# LCDTFT_CTRL_BT817_818.net
KiCad netlist of a schematic drawn in Altium Designer
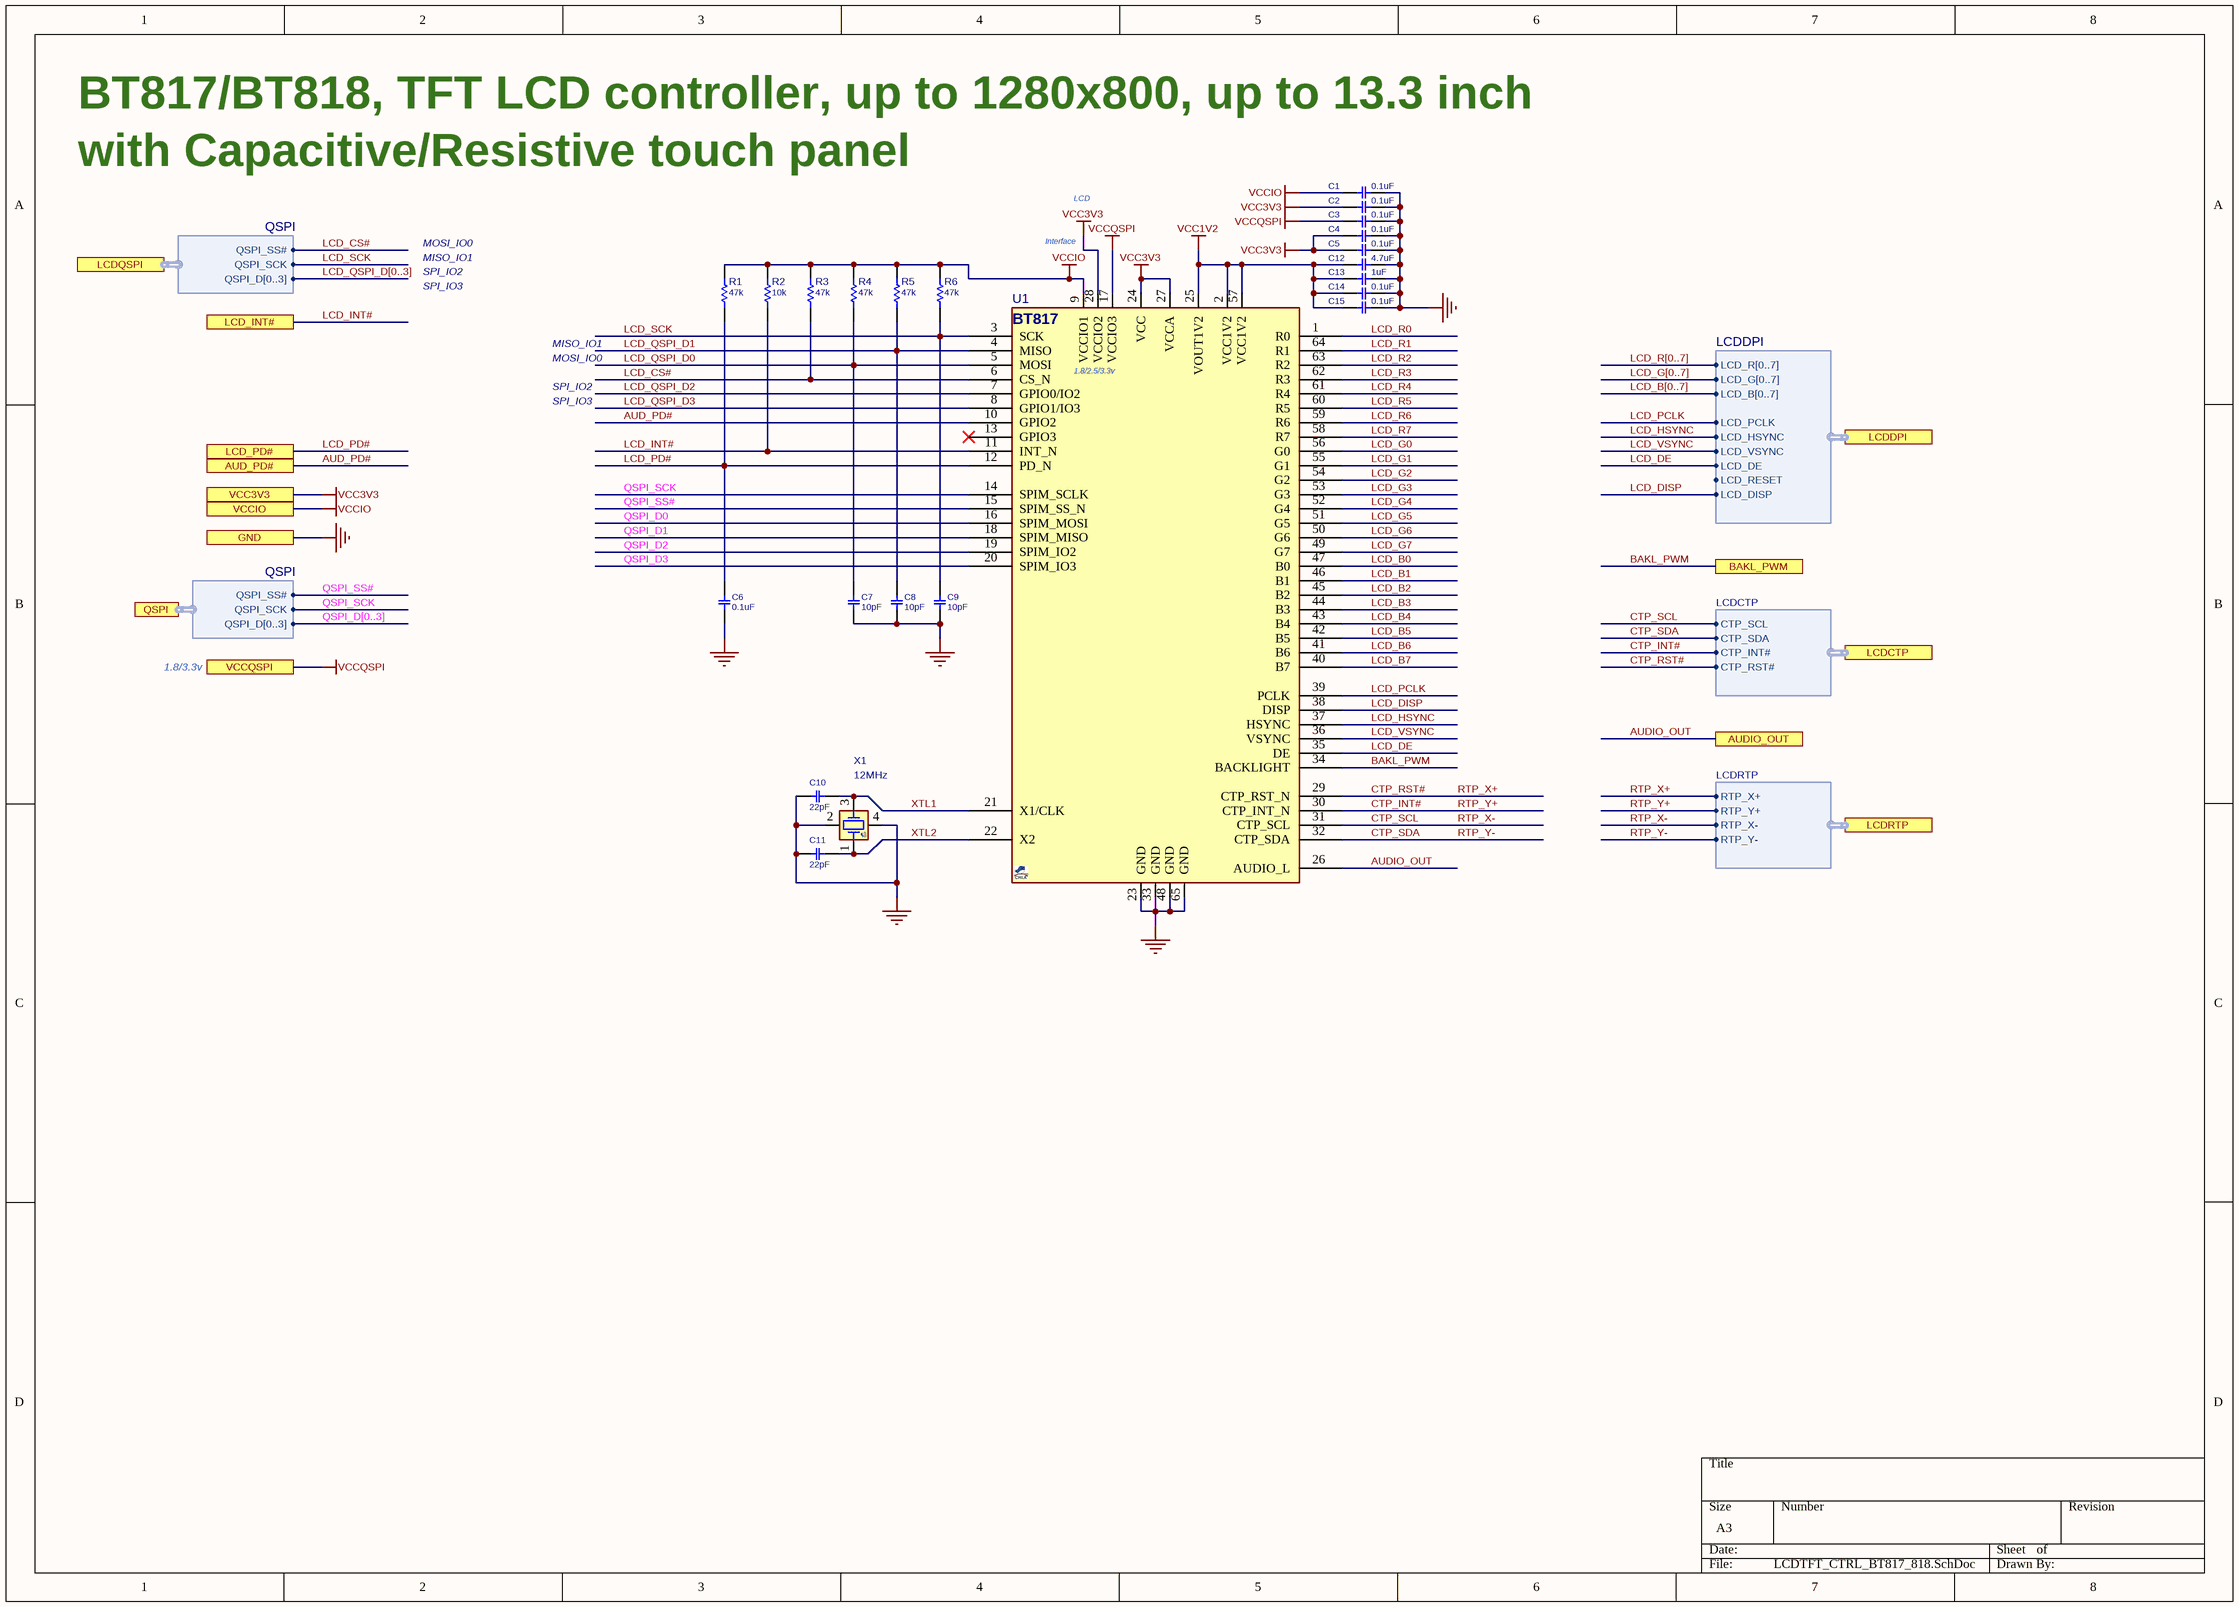
[diagram p0: LCDTFT_CTRL_BT817_818.SchDoc]

(export (version "E")
  (design (tool "Eeschema 10.0.6"))
  (components
    (comp (ref "C1")
      (value "0.1uF")
      (footprint "C0402")
      (description "CAP, MLCC")
      (fields (field (name "MANF_P#") "GRM155R71H104KE14D") (field (name "MANF") "Murata"))
      (libsource (lib "passive_smd") (part "CAP_SMD_MLCC"))
    )
    (comp (ref "C2")
      (value "0.1uF")
      (footprint "C0402")
      (description "CAP, MLCC")
      (fields (field (name "MANF_P#") "GRM155R71H104KE14D") (field (name "MANF") "Murata"))
      (libsource (lib "passive_smd") (part "CAP_SMD_MLCC"))
    )
    (comp (ref "C3")
      (value "0.1uF")
      (footprint "C0402")
      (description "CAP, MLCC")
      (fields (field (name "MANF_P#") "GRM155R71H104KE14D") (field (name "MANF") "Murata"))
      (libsource (lib "passive_smd") (part "CAP_SMD_MLCC"))
    )
    (comp (ref "C4")
      (value "0.1uF")
      (footprint "C0402")
      (description "CAP, MLCC")
      (fields (field (name "MANF_P#") "GRM155R71H104KE14D") (field (name "MANF") "Murata"))
      (libsource (lib "passive_smd") (part "CAP_SMD_MLCC"))
    )
    (comp (ref "C5")
      (value "0.1uF")
      (footprint "C0402")
      (description "CAP, MLCC")
      (fields (field (name "MANF_P#") "GRM155R71H104KE14D") (field (name "MANF") "Murata"))
      (libsource (lib "passive_smd") (part "CAP_SMD_MLCC"))
    )
    (comp (ref "C6")
      (value "0.1uF")
      (footprint "C0402")
      (description "CAP, MLCC")
      (fields (field (name "MANF_P#") "GRM155R71H104KE14D") (field (name "MANF") "Murata"))
      (libsource (lib "passive_smd") (part "CAP_SMD_MLCC"))
    )
    (comp (ref "C7")
      (value "10pF")
      (footprint "C0402")
      (description "CAP, MLCC")
      (libsource (lib "passive_smd") (part "CAP_SMD_MLCC"))
    )
    (comp (ref "C8")
      (value "10pF")
      (footprint "C0402")
      (description "CAP, MLCC")
      (libsource (lib "passive_smd") (part "CAP_SMD_MLCC"))
    )
    (comp (ref "C9")
      (value "10pF")
      (footprint "C0402")
      (description "CAP, MLCC")
      (libsource (lib "passive_smd") (part "CAP_SMD_MLCC"))
    )
    (comp (ref "C10")
      (value "22pF")
      (footprint "C0402")
      (description "CAP, MLCC")
      (libsource (lib "passive_smd") (part "CAP_SMD_MLCC"))
    )
    (comp (ref "C11")
      (value "22pF")
      (footprint "C0402")
      (description "CAP, MLCC")
      (libsource (lib "passive_smd") (part "CAP_SMD_MLCC"))
    )
    (comp (ref "C12")
      (value "4.7uF")
      (footprint "C0402")
      (description "CAP, MLCC")
      (libsource (lib "passive_smd") (part "CAP_SMD_MLCC"))
    )
    (comp (ref "C13")
      (value "1uF")
      (footprint "C0402")
      (description "CAP, MLCC")
      (libsource (lib "passive_smd") (part "CAP_SMD_MLCC"))
    )
    (comp (ref "C14")
      (value "0.1uF")
      (footprint "C0402")
      (description "CAP, MLCC")
      (fields (field (name "MANF_P#") "GRM155R71H104KE14D") (field (name "MANF") "Murata"))
      (libsource (lib "passive_smd") (part "CAP_SMD_MLCC"))
    )
    (comp (ref "C15")
      (value "0.1uF")
      (footprint "C0402")
      (description "CAP, MLCC")
      (fields (field (name "MANF_P#") "GRM155R71H104KE14D") (field (name "MANF") "Murata"))
      (libsource (lib "passive_smd") (part "CAP_SMD_MLCC"))
    )
    (comp (ref "R1")
      (value "47k")
      (footprint "R0402")
      (description "RESISTOR, SMD")
      (libsource (lib "passive_res_smd") (part "RES_SMD"))
    )
    (comp (ref "R2")
      (value "10k")
      (footprint "R0402")
      (description "RESISTOR, SMD")
      (libsource (lib "passive_res_smd") (part "RES_SMD"))
    )
    (comp (ref "R3")
      (value "47k")
      (footprint "R0402")
      (description "RESISTOR, SMD")
      (libsource (lib "passive_res_smd") (part "RES_SMD"))
    )
    (comp (ref "R4")
      (value "47k")
      (footprint "R0402")
      (description "RESISTOR, SMD")
      (libsource (lib "passive_res_smd") (part "RES_SMD"))
    )
    (comp (ref "R5")
      (value "47k")
      (footprint "R0402")
      (description "RESISTOR, SMD")
      (libsource (lib "passive_res_smd") (part "RES_SMD"))
    )
    (comp (ref "R6")
      (value "47k")
      (footprint "R0402")
      (description "RESISTOR, SMD")
      (libsource (lib "passive_res_smd") (part "RES_SMD"))
    )
    (comp (ref "U1")
      (value "BT817")
      (footprint "QFN50_64T")
      (description "LCD Display Controller, Embedded Video Engine, 1280X800, QFN-64")
      (fields (field (name "MANF") "FTDI/Bridgetek") (field (name "MANF_P#") "BT817Q"))
      (libsource (lib "lcdtft_controller") (part "BT817_QFN64"))
    )
    (comp (ref "X1")
      (value "12MHz")
      (footprint "XTL_4_3225")
      (description "Crystal 12MHz")
      (fields (field (name "MANF") "ECS") (field (name "MANF_P#") "ECS-120-18-33-JEM-TR"))
      (libsource (lib "crystal") (part "XTL_4_12MHz_3225"))
    )
  )
  (nets
    (net (code "5") (name "/AUDIO_OUT") (class "Default")
      (node (ref "U1") (pin "26") (pinfunction "AUDIO_L_26") (pintype "passive"))
    )
    (net (code "6") (name "/AUD_PD#") (class "Default")
      (node (ref "U1") (pin "10") (pinfunction "GPIO2_10") (pintype "passive"))
    )
    (net (code "7") (name "/BAKL_PWM") (class "Default")
      (node (ref "U1") (pin "34") (pinfunction "BACKLIGHT_34") (pintype "passive"))
    )
    (net (code "8") (name "/CTP_INT#") (class "Default")
      (node (ref "U1") (pin "30") (pinfunction "CTP_INT_N_30") (pintype "passive"))
    )
    (net (code "9") (name "/CTP_RST#") (class "Default")
      (node (ref "U1") (pin "29") (pinfunction "CTP_RST_N_29") (pintype "passive"))
    )
    (net (code "10") (name "/CTP_SCL") (class "Default")
      (node (ref "U1") (pin "31") (pinfunction "CTP_SCL_31") (pintype "passive"))
    )
    (net (code "11") (name "/CTP_SDA") (class "Default")
      (node (ref "U1") (pin "32") (pinfunction "CTP_SDA_32") (pintype "passive"))
    )
    (net (code "12") (name "/LCD_B0") (class "Default")
      (node (ref "U1") (pin "47") (pinfunction "B0_47") (pintype "passive"))
    )
    (net (code "13") (name "/LCD_B1") (class "Default")
      (node (ref "U1") (pin "46") (pinfunction "B1_46") (pintype "passive"))
    )
    (net (code "14") (name "/LCD_B2") (class "Default")
      (node (ref "U1") (pin "45") (pinfunction "B2_45") (pintype "passive"))
    )
    (net (code "15") (name "/LCD_B3") (class "Default")
      (node (ref "U1") (pin "44") (pinfunction "B3_44") (pintype "passive"))
    )
    (net (code "16") (name "/LCD_B4") (class "Default")
      (node (ref "U1") (pin "43") (pinfunction "B4_43") (pintype "passive"))
    )
    (net (code "17") (name "/LCD_B5") (class "Default")
      (node (ref "U1") (pin "42") (pinfunction "B5_42") (pintype "passive"))
    )
    (net (code "18") (name "/LCD_B6") (class "Default")
      (node (ref "U1") (pin "41") (pinfunction "B6_41") (pintype "passive"))
    )
    (net (code "19") (name "/LCD_B7") (class "Default")
      (node (ref "U1") (pin "40") (pinfunction "B7_40") (pintype "passive"))
    )
    (net (code "21") (name "/LCD_CS#") (class "Default")
      (node (ref "R3") (pin "2") (pinfunction "2_2") (pintype "passive"))
      (node (ref "U1") (pin "6") (pinfunction "CS_N_6") (pintype "passive"))
    )
    (net (code "22") (name "/LCD_DE") (class "Default")
      (node (ref "U1") (pin "35") (pinfunction "DE_35") (pintype "passive"))
    )
    (net (code "23") (name "/LCD_DISP") (class "Default")
      (node (ref "U1") (pin "38") (pinfunction "DISP_38") (pintype "passive"))
    )
    (net (code "24") (name "/LCD_G0") (class "Default")
      (node (ref "U1") (pin "56") (pinfunction "G0_56") (pintype "passive"))
    )
    (net (code "25") (name "/LCD_G1") (class "Default")
      (node (ref "U1") (pin "55") (pinfunction "G1_55") (pintype "passive"))
    )
    (net (code "26") (name "/LCD_G2") (class "Default")
      (node (ref "U1") (pin "54") (pinfunction "G2_54") (pintype "passive"))
    )
    (net (code "27") (name "/LCD_G3") (class "Default")
      (node (ref "U1") (pin "53") (pinfunction "G3_53") (pintype "passive"))
    )
    (net (code "28") (name "/LCD_G4") (class "Default")
      (node (ref "U1") (pin "52") (pinfunction "G4_52") (pintype "passive"))
    )
    (net (code "29") (name "/LCD_G5") (class "Default")
      (node (ref "U1") (pin "51") (pinfunction "G5_51") (pintype "passive"))
    )
    (net (code "30") (name "/LCD_G6") (class "Default")
      (node (ref "U1") (pin "50") (pinfunction "G6_50") (pintype "passive"))
    )
    (net (code "31") (name "/LCD_G7") (class "Default")
      (node (ref "U1") (pin "49") (pinfunction "G7_49") (pintype "passive"))
    )
    (net (code "33") (name "/LCD_HSYNC") (class "Default")
      (node (ref "U1") (pin "37") (pinfunction "HSYNC_37") (pintype "passive"))
    )
    (net (code "34") (name "/LCD_INT#") (class "Default")
      (node (ref "R2") (pin "2") (pinfunction "2_2") (pintype "passive"))
      (node (ref "U1") (pin "11") (pinfunction "INT_N_11") (pintype "passive"))
    )
    (net (code "35") (name "/LCD_PCLK") (class "Default")
      (node (ref "U1") (pin "39") (pinfunction "PCLK_39") (pintype "passive"))
    )
    (net (code "36") (name "/LCD_PD#") (class "Default")
      (node (ref "C6") (pin "1") (pinfunction "1_1") (pintype "passive"))
      (node (ref "R1") (pin "2") (pinfunction "2_2") (pintype "passive"))
      (node (ref "U1") (pin "12") (pinfunction "PD_N_12") (pintype "passive"))
    )
    (net (code "37") (name "/LCD_QSPI_D0") (class "Default")
      (node (ref "C7") (pin "1") (pinfunction "1_1") (pintype "passive"))
      (node (ref "R4") (pin "2") (pinfunction "2_2") (pintype "passive"))
      (node (ref "U1") (pin "5") (pinfunction "MOSI_5") (pintype "passive"))
    )
    (net (code "38") (name "/LCD_QSPI_D1") (class "Default")
      (node (ref "C8") (pin "1") (pinfunction "1_1") (pintype "passive"))
      (node (ref "R5") (pin "2") (pinfunction "2_2") (pintype "passive"))
      (node (ref "U1") (pin "4") (pinfunction "MISO_4") (pintype "passive"))
    )
    (net (code "39") (name "/LCD_QSPI_D2") (class "Default")
      (node (ref "U1") (pin "7") (pinfunction "GPIO0/IO2_7") (pintype "passive"))
    )
    (net (code "40") (name "/LCD_QSPI_D3") (class "Default")
      (node (ref "U1") (pin "8") (pinfunction "GPIO1/IO3_8") (pintype "passive"))
    )
    (net (code "42") (name "/LCD_R0") (class "Default")
      (node (ref "U1") (pin "1") (pinfunction "R0_1") (pintype "passive"))
    )
    (net (code "43") (name "/LCD_R1") (class "Default")
      (node (ref "U1") (pin "64") (pinfunction "R1_64") (pintype "passive"))
    )
    (net (code "44") (name "/LCD_R2") (class "Default")
      (node (ref "U1") (pin "63") (pinfunction "R2_63") (pintype "passive"))
    )
    (net (code "45") (name "/LCD_R3") (class "Default")
      (node (ref "U1") (pin "62") (pinfunction "R3_62") (pintype "passive"))
    )
    (net (code "46") (name "/LCD_R4") (class "Default")
      (node (ref "U1") (pin "61") (pinfunction "R4_61") (pintype "passive"))
    )
    (net (code "47") (name "/LCD_R5") (class "Default")
      (node (ref "U1") (pin "60") (pinfunction "R5_60") (pintype "passive"))
    )
    (net (code "48") (name "/LCD_R6") (class "Default")
      (node (ref "U1") (pin "59") (pinfunction "R6_59") (pintype "passive"))
    )
    (net (code "49") (name "/LCD_R7") (class "Default")
      (node (ref "U1") (pin "58") (pinfunction "R7_58") (pintype "passive"))
    )
    (net (code "51") (name "/LCD_SCK") (class "Default")
      (node (ref "C9") (pin "1") (pinfunction "1_1") (pintype "passive"))
      (node (ref "R6") (pin "2") (pinfunction "2_2") (pintype "passive"))
      (node (ref "U1") (pin "3") (pinfunction "SCK_3") (pintype "passive"))
    )
    (net (code "52") (name "/LCD_VSYNC") (class "Default")
      (node (ref "U1") (pin "36") (pinfunction "VSYNC_36") (pintype "passive"))
    )
    (net (code "53") (name "/QSPI_D0") (class "Default")
      (node (ref "U1") (pin "16") (pinfunction "SPIM_MOSI_16") (pintype "passive"))
    )
    (net (code "54") (name "/QSPI_D1") (class "Default")
      (node (ref "U1") (pin "18") (pinfunction "SPIM_MISO_18") (pintype "passive"))
    )
    (net (code "55") (name "/QSPI_D2") (class "Default")
      (node (ref "U1") (pin "19") (pinfunction "SPIM_IO2_19") (pintype "passive"))
    )
    (net (code "56") (name "/QSPI_D3") (class "Default")
      (node (ref "U1") (pin "20") (pinfunction "SPIM_IO3_20") (pintype "passive"))
    )
    (net (code "58") (name "/QSPI_SCK") (class "Default")
      (node (ref "U1") (pin "14") (pinfunction "SPIM_SCLK_14") (pintype "passive"))
    )
    (net (code "59") (name "/QSPI_SS#") (class "Default")
      (node (ref "U1") (pin "15") (pinfunction "SPIM_SS_N_15") (pintype "passive"))
    )
    (net (code "60") (name "/XTL1") (class "Default")
      (node (ref "C10") (pin "2") (pinfunction "2_2") (pintype "passive"))
      (node (ref "U1") (pin "21") (pinfunction "X1/CLK_21") (pintype "passive"))
      (node (ref "X1") (pin "3") (pinfunction "2_3") (pintype "passive"))
    )
    (net (code "61") (name "/XTL2") (class "Default")
      (node (ref "C11") (pin "1") (pinfunction "1_1") (pintype "passive"))
      (node (ref "U1") (pin "22") (pinfunction "X2_22") (pintype "passive"))
      (node (ref "X1") (pin "1") (pinfunction "1_1") (pintype "passive"))
    )
    (net (code "66") (name "GND") (class "Default")
      (node (ref "C1") (pin "1") (pinfunction "1_1") (pintype "passive"))
      (node (ref "C10") (pin "1") (pinfunction "1_1") (pintype "passive"))
      (node (ref "C11") (pin "2") (pinfunction "2_2") (pintype "passive"))
      (node (ref "C12") (pin "1") (pinfunction "1_1") (pintype "passive"))
      (node (ref "C13") (pin "1") (pinfunction "1_1") (pintype "passive"))
      (node (ref "C14") (pin "1") (pinfunction "1_1") (pintype "passive"))
      (node (ref "C15") (pin "1") (pinfunction "1_1") (pintype "passive"))
      (node (ref "C2") (pin "1") (pinfunction "1_1") (pintype "passive"))
      (node (ref "C3") (pin "1") (pinfunction "1_1") (pintype "passive"))
      (node (ref "C4") (pin "1") (pinfunction "1_1") (pintype "passive"))
      (node (ref "C5") (pin "1") (pinfunction "1_1") (pintype "passive"))
      (node (ref "C6") (pin "2") (pinfunction "2_2") (pintype "passive"))
      (node (ref "C7") (pin "2") (pinfunction "2_2") (pintype "passive"))
      (node (ref "C8") (pin "2") (pinfunction "2_2") (pintype "passive"))
      (node (ref "C9") (pin "2") (pinfunction "2_2") (pintype "passive"))
      (node (ref "U1") (pin "23") (pinfunction "GND_23") (pintype "passive"))
      (node (ref "U1") (pin "33") (pinfunction "GND_33") (pintype "passive"))
      (node (ref "U1") (pin "48") (pinfunction "GND_48") (pintype "passive"))
      (node (ref "U1") (pin "65") (pinfunction "GND_65") (pintype "passive"))
      (node (ref "X1") (pin "2") (pinfunction "2_2") (pintype "passive"))
      (node (ref "X1") (pin "4") (pinfunction "4_4") (pintype "passive"))
    )
    (net (code "67") (name "VCC1V2") (class "Default")
      (node (ref "C12") (pin "2") (pinfunction "2_2") (pintype "passive"))
      (node (ref "C13") (pin "2") (pinfunction "2_2") (pintype "passive"))
      (node (ref "C14") (pin "2") (pinfunction "2_2") (pintype "passive"))
      (node (ref "C15") (pin "2") (pinfunction "2_2") (pintype "passive"))
      (node (ref "U1") (pin "2") (pinfunction "VCC1V2_2") (pintype "passive"))
      (node (ref "U1") (pin "25") (pinfunction "VOUT1V2_25") (pintype "passive"))
      (node (ref "U1") (pin "57") (pinfunction "VCC1V2_57") (pintype "passive"))
    )
    (net (code "68") (name "VCC3V3") (class "Default")
      (node (ref "C2") (pin "2") (pinfunction "2_2") (pintype "passive"))
      (node (ref "C4") (pin "2") (pinfunction "2_2") (pintype "passive"))
      (node (ref "C5") (pin "2") (pinfunction "2_2") (pintype "passive"))
      (node (ref "U1") (pin "24") (pinfunction "VCC_24") (pintype "passive"))
      (node (ref "U1") (pin "27") (pinfunction "VCCA_27") (pintype "passive"))
      (node (ref "U1") (pin "28") (pinfunction "VCCIO2_28") (pintype "passive"))
    )
    (net (code "69") (name "VCCIO") (class "Default")
      (node (ref "C1") (pin "2") (pinfunction "2_2") (pintype "passive"))
      (node (ref "R1") (pin "1") (pinfunction "1_1") (pintype "passive"))
      (node (ref "R2") (pin "1") (pinfunction "1_1") (pintype "passive"))
      (node (ref "R3") (pin "1") (pinfunction "1_1") (pintype "passive"))
      (node (ref "R4") (pin "1") (pinfunction "1_1") (pintype "passive"))
      (node (ref "R5") (pin "1") (pinfunction "1_1") (pintype "passive"))
      (node (ref "R6") (pin "1") (pinfunction "1_1") (pintype "passive"))
      (node (ref "U1") (pin "9") (pinfunction "VCCIO1_9") (pintype "passive"))
    )
    (net (code "70") (name "VCCQSPI") (class "Default")
      (node (ref "C3") (pin "2") (pinfunction "2_2") (pintype "passive"))
      (node (ref "U1") (pin "17") (pinfunction "VCCIO3_17") (pintype "passive"))
    )
    (net (code "71") (name "unconnected-(U1-GPIO3-Pad13)") (class "Default")
      (node (ref "U1") (pin "13") (pinfunction "GPIO3_13") (pintype "passive+no_connect"))
    )
  )
)
